# EDGAR_00.net
KiCad netlist of a schematic drawn in Altium Designer
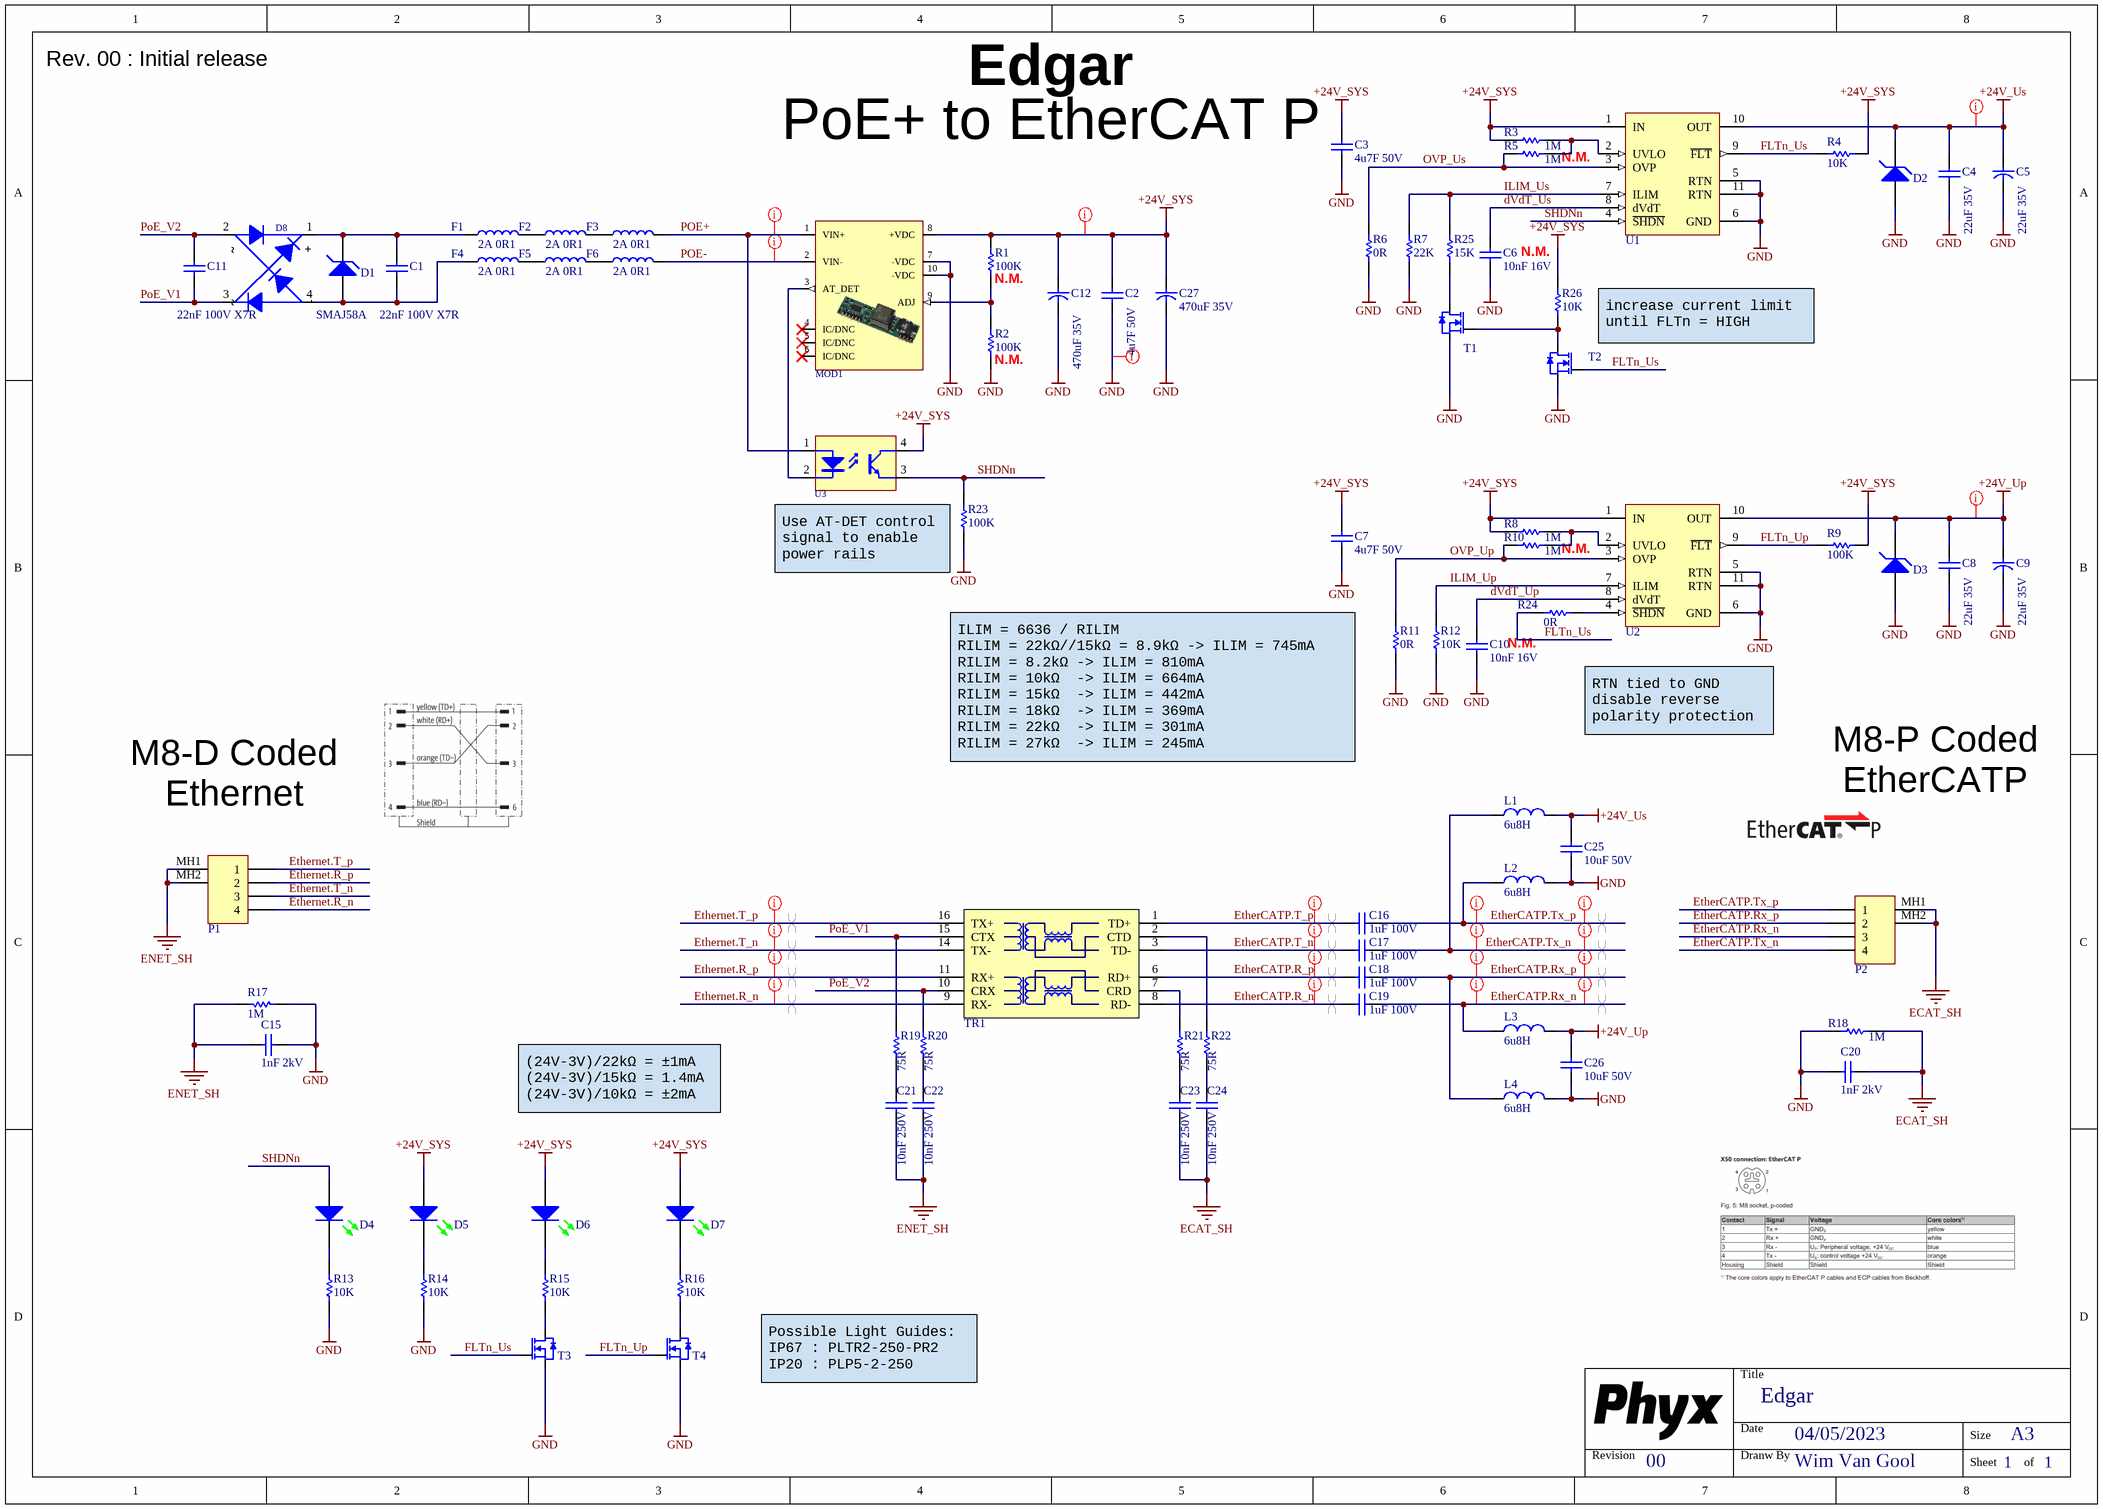
[diagram p0: EDGAR_00.SchDoc]

(export (version "E")
  (design (tool "Eeschema 10.0.6"))
  (components
    (comp (ref "C1")
      (value "22nF 100V X7R")
      (footprint "C0603_N")
      (description "Capacitor Ceramic")
      (fields (field (name "Comment") "CAP_CERAMIC"))
      (libsource (lib "Phyx_Components") (part "CAP_CERAMIC"))
    )
    (comp (ref "C2")
      (value "4u7F 50V")
      (footprint "C1210_N")
      (description "Capacitor Ceramic")
      (fields (field (name "Comment") "CAP_CERAMIC"))
      (libsource (lib "Phyx_Components") (part "CAP_CERAMIC"))
    )
    (comp (ref "C3")
      (value "4u7F 50V")
      (footprint "C1210_N")
      (description "Capacitor Ceramic")
      (fields (field (name "Comment") "CAP_CERAMIC"))
      (libsource (lib "Phyx_Components") (part "CAP_CERAMIC"))
    )
    (comp (ref "C4")
      (value "22uF 35V")
      (footprint "C1206_N")
      (description "Capacitor Ceramic")
      (fields (field (name "Comment") "CAP_CERAMIC"))
      (libsource (lib "Phyx_Components") (part "CAP_CERAMIC"))
    )
    (comp (ref "C5")
      (value "22uF 35V")
      (footprint "C6.6x5.4")
      (description "Capacitor electrolyt")
      (fields (field (name "Comment") "CAP_POL"))
      (libsource (lib "Phyx_Components") (part "CAP_POL"))
    )
    (comp (ref "C6")
      (value "10nF 16V")
      (footprint "C0603_N")
      (description "Capacitor Ceramic")
      (fields (field (name "Comment") "CAP_CERAMIC"))
      (libsource (lib "Phyx_Components") (part "CAP_CERAMIC"))
    )
    (comp (ref "C7")
      (value "4u7F 50V")
      (footprint "C1210_N")
      (description "Capacitor Ceramic")
      (fields (field (name "Comment") "CAP_CERAMIC"))
      (libsource (lib "Phyx_Components") (part "CAP_CERAMIC"))
    )
    (comp (ref "C8")
      (value "22uF 35V")
      (footprint "C1206_N")
      (description "Capacitor Ceramic")
      (fields (field (name "Comment") "CAP_CERAMIC"))
      (libsource (lib "Phyx_Components") (part "CAP_CERAMIC"))
    )
    (comp (ref "C9")
      (value "22uF 35V")
      (footprint "C6.6x5.4")
      (description "Capacitor electrolyt")
      (fields (field (name "Comment") "CAP_POL"))
      (libsource (lib "Phyx_Components") (part "CAP_POL"))
    )
    (comp (ref "C10")
      (value "10nF 16V")
      (footprint "C0603_N")
      (description "Capacitor Ceramic")
      (fields (field (name "Comment") "CAP_CERAMIC"))
      (libsource (lib "Phyx_Components") (part "CAP_CERAMIC"))
    )
    (comp (ref "C11")
      (value "22nF 100V X7R")
      (footprint "C0603_N")
      (description "Capacitor Ceramic")
      (fields (field (name "Comment") "CAP_CERAMIC"))
      (libsource (lib "Phyx_Components") (part "CAP_CERAMIC"))
    )
    (comp (ref "C12")
      (value "470uF 35V")
      (footprint "C10x10.2")
      (description "Capacitor electrolyt")
      (fields (field (name "Comment") "CAP_POL"))
      (libsource (lib "Phyx_Components") (part "CAP_POL"))
    )
    (comp (ref "C15")
      (value "1nF 2kV")
      (footprint "C1206_N")
      (description "Capacitor Ceramic")
      (fields (field (name "Comment") "CAP_CERAMIC"))
      (libsource (lib "Phyx_Components") (part "CAP_CERAMIC"))
    )
    (comp (ref "C16")
      (value "1uF 100V")
      (footprint "C1206_N")
      (description "Capacitor Ceramic")
      (fields (field (name "Comment") "CAP_CERAMIC"))
      (libsource (lib "Phyx_Components") (part "CAP_CERAMIC"))
    )
    (comp (ref "C17")
      (value "1uF 100V")
      (footprint "C1206_N")
      (description "Capacitor Ceramic")
      (fields (field (name "Comment") "CAP_CERAMIC"))
      (libsource (lib "Phyx_Components") (part "CAP_CERAMIC"))
    )
    (comp (ref "C18")
      (value "1uF 100V")
      (footprint "C1206_N")
      (description "Capacitor Ceramic")
      (fields (field (name "Comment") "CAP_CERAMIC"))
      (libsource (lib "Phyx_Components") (part "CAP_CERAMIC"))
    )
    (comp (ref "C19")
      (value "1uF 100V")
      (footprint "C1206_N")
      (description "Capacitor Ceramic")
      (fields (field (name "Comment") "CAP_CERAMIC"))
      (libsource (lib "Phyx_Components") (part "CAP_CERAMIC"))
    )
    (comp (ref "C20")
      (value "1nF 2kV")
      (footprint "C1206_N")
      (description "Capacitor Ceramic")
      (fields (field (name "Comment") "CAP_CERAMIC"))
      (libsource (lib "Phyx_Components") (part "CAP_CERAMIC"))
    )
    (comp (ref "C21")
      (value "10nF 250V")
      (footprint "C1206_N")
      (description "Capacitor Ceramic")
      (fields (field (name "Comment") "CAP_CERAMIC"))
      (libsource (lib "Phyx_Components") (part "CAP_CERAMIC"))
    )
    (comp (ref "C22")
      (value "10nF 250V")
      (footprint "C1206_N")
      (description "Capacitor Ceramic")
      (fields (field (name "Comment") "CAP_CERAMIC"))
      (libsource (lib "Phyx_Components") (part "CAP_CERAMIC"))
    )
    (comp (ref "C23")
      (value "10nF 250V")
      (footprint "C1206_N")
      (description "Capacitor Ceramic")
      (fields (field (name "Comment") "CAP_CERAMIC"))
      (libsource (lib "Phyx_Components") (part "CAP_CERAMIC"))
    )
    (comp (ref "C24")
      (value "10nF 250V")
      (footprint "C1206_N")
      (description "Capacitor Ceramic")
      (fields (field (name "Comment") "CAP_CERAMIC"))
      (libsource (lib "Phyx_Components") (part "CAP_CERAMIC"))
    )
    (comp (ref "C25")
      (value "10uF 50V")
      (footprint "C1206_N")
      (description "Capacitor Ceramic")
      (fields (field (name "Comment") "CAP_CERAMIC"))
      (libsource (lib "Phyx_Components") (part "CAP_CERAMIC"))
    )
    (comp (ref "C26")
      (value "10uF 50V")
      (footprint "C1206_N")
      (description "Capacitor Ceramic")
      (fields (field (name "Comment") "CAP_CERAMIC"))
      (libsource (lib "Phyx_Components") (part "CAP_CERAMIC"))
    )
    (comp (ref "C27")
      (value "470uF 35V")
      (footprint "C_12.5x14_5mm")
      (description "Capacitor electrolyt")
      (fields (field (name "Comment") "URZ1V471MHD"))
      (libsource (lib "Phyx_Components") (part "CAP_POL"))
    )
    (comp (ref "D1")
      (value "SMAJ58A")
      (footprint "SMA_AC")
      (fields (field (name "Comment") "TVS Diode 58V 400W Unidirectional DO-214AC SMA"))
      (libsource (lib "Phyx_Components") (part "TVS_AC"))
    )
    (comp (ref "D2")
      (value "TVS Diode 24V 400W Unidirectional DO-214AC SMA")
      (footprint "SMA_AC")
      (description "=Description")
      (libsource (lib "Phyx_Components") (part "TVS_AC"))
    )
    (comp (ref "D3")
      (value "TVS Diode 24V 400W Unidirectional DO-214AC SMA")
      (footprint "SMA_AC")
      (description "=Description")
      (libsource (lib "Phyx_Components") (part "TVS_AC"))
    )
    (comp (ref "D4")
      (value "Default 0805 Green LED")
      (footprint "LED_0805_GR")
      (description "=Description")
      (libsource (lib "Phyx_Components") (part "LED_GREEN"))
    )
    (comp (ref "D5")
      (value "Default 0805 Green LED")
      (footprint "LED_0805_GR")
      (description "=Description")
      (libsource (lib "Phyx_Components") (part "LED_GREEN"))
    )
    (comp (ref "D6")
      (value "Default 0805 Green LED")
      (footprint "LED_0805_GR")
      (description "=Description")
      (libsource (lib "Phyx_Components") (part "LED_GREEN"))
    )
    (comp (ref "D7")
      (value "Default 0805 Green LED")
      (footprint "LED_0805_GR")
      (description "=Description")
      (libsource (lib "Phyx_Components") (part "LED_GREEN"))
    )
    (comp (ref "D8")
      (value "Bridge Rectifier 100V 2A CD-HD201")
      (footprint "BRNS_CD_HD2x")
      (description "=Description")
      (libsource (lib "Phyx_Components") (part "BRNS_CD_HD2x"))
    )
    (comp (ref "F1")
      (value "2A 0R1")
      (footprint "L0805")
      (fields (field (name "Comment") "FERRITE"))
      (libsource (lib "Phyx_Components") (part "FERRITE"))
    )
    (comp (ref "F2")
      (value "2A 0R1")
      (footprint "L0805")
      (fields (field (name "Comment") "FERRITE"))
      (libsource (lib "Phyx_Components") (part "FERRITE"))
    )
    (comp (ref "F3")
      (value "2A 0R1")
      (footprint "L0805")
      (fields (field (name "Comment") "FERRITE"))
      (libsource (lib "Phyx_Components") (part "FERRITE"))
    )
    (comp (ref "F4")
      (value "2A 0R1")
      (footprint "L0805")
      (fields (field (name "Comment") "FERRITE"))
      (libsource (lib "Phyx_Components") (part "FERRITE"))
    )
    (comp (ref "F5")
      (value "2A 0R1")
      (footprint "L0805")
      (fields (field (name "Comment") "FERRITE"))
      (libsource (lib "Phyx_Components") (part "FERRITE"))
    )
    (comp (ref "F6")
      (value "2A 0R1")
      (footprint "L0805")
      (fields (field (name "Comment") "FERRITE"))
      (libsource (lib "Phyx_Components") (part "FERRITE"))
    )
    (comp (ref "L1")
      (value "6u8H")
      (footprint "WE_WE-LHMI_5020")
      (fields (field (name "Comment") "74437334068"))
      (libsource (lib "Phyx_Components") (part "INDUCTOR"))
    )
    (comp (ref "L2")
      (value "6u8H")
      (footprint "WE_WE-LHMI_5020")
      (fields (field (name "Comment") "74437334068"))
      (libsource (lib "Phyx_Components") (part "INDUCTOR"))
    )
    (comp (ref "L3")
      (value "6u8H")
      (footprint "WE_WE-LHMI_5020")
      (fields (field (name "Comment") "74437334068"))
      (libsource (lib "Phyx_Components") (part "INDUCTOR"))
    )
    (comp (ref "L4")
      (value "6u8H")
      (footprint "WE_WE-LHMI_5020")
      (fields (field (name "Comment") "74437334068"))
      (libsource (lib "Phyx_Components") (part "INDUCTOR"))
    )
    (comp (ref "MOD1")
      (value "PoE+ Module 24V 30W 802.3at Silvertel Ag5424")
      (footprint "SIL_Ag5400")
      (description "=Description")
      (libsource (lib "Phyx_Components") (part "SIL_Ag5400"))
    )
    (comp (ref "P1")
      (value "Receptacle, M8, female, straight, 4 poles, D-coded, back wall-mounting, print contact, shielded, Industrial Ethernet")
      (footprint "ESCHA_8089337")
      (libsource (lib "Phyx_Components") (part "Header 4_MH2"))
    )
    (comp (ref "P2")
      (value "Receptacle, M8, female, straight, 4 poles, P-coded, back wall-mounting, print contact, shielded, EtherCATP")
      (footprint "ESCHA_8089341")
      (libsource (lib "") (part "Header 4_MH2_1"))
    )
    (comp (ref "R1")
      (value "100K")
      (footprint "R0603_N")
      (fields (field (name "Comment") "RESISTOR"))
      (libsource (lib "Phyx_Components") (part "RESISTOR"))
    )
    (comp (ref "R2")
      (value "100K")
      (footprint "R0603_N")
      (fields (field (name "Comment") "RESISTOR"))
      (libsource (lib "Phyx_Components") (part "RESISTOR"))
    )
    (comp (ref "R3")
      (value "1M")
      (footprint "R0603_N")
      (fields (field (name "Comment") "RESISTOR"))
      (libsource (lib "Phyx_Components") (part "RESISTOR"))
    )
    (comp (ref "R4")
      (value "10K")
      (footprint "R0603_N")
      (fields (field (name "Comment") "RESISTOR"))
      (libsource (lib "Phyx_Components") (part "RESISTOR"))
    )
    (comp (ref "R5")
      (value "1M")
      (footprint "R0603_N")
      (fields (field (name "Comment") "RESISTOR"))
      (libsource (lib "Phyx_Components") (part "RESISTOR"))
    )
    (comp (ref "R6")
      (value "0R")
      (footprint "R0603_N")
      (fields (field (name "Comment") "RESISTOR"))
      (libsource (lib "Phyx_Components") (part "RESISTOR"))
    )
    (comp (ref "R7")
      (value "22K")
      (footprint "R0603_N")
      (fields (field (name "Comment") "RESISTOR"))
      (libsource (lib "Phyx_Components") (part "RESISTOR"))
    )
    (comp (ref "R8")
      (value "1M")
      (footprint "R0603_N")
      (fields (field (name "Comment") "RESISTOR"))
      (libsource (lib "Phyx_Components") (part "RESISTOR"))
    )
    (comp (ref "R9")
      (value "100K")
      (footprint "R0603_N")
      (fields (field (name "Comment") "RESISTOR"))
      (libsource (lib "Phyx_Components") (part "RESISTOR"))
    )
    (comp (ref "R10")
      (value "1M")
      (footprint "R0603_N")
      (fields (field (name "Comment") "RESISTOR"))
      (libsource (lib "Phyx_Components") (part "RESISTOR"))
    )
    (comp (ref "R11")
      (value "0R")
      (footprint "R0603_N")
      (fields (field (name "Comment") "RESISTOR"))
      (libsource (lib "Phyx_Components") (part "RESISTOR"))
    )
    (comp (ref "R12")
      (value "10K")
      (footprint "R0603_N")
      (fields (field (name "Comment") "RESISTOR"))
      (libsource (lib "Phyx_Components") (part "RESISTOR"))
    )
    (comp (ref "R13")
      (value "10K")
      (footprint "R0603_N")
      (fields (field (name "Comment") "RESISTOR"))
      (libsource (lib "Phyx_Components") (part "RESISTOR"))
    )
    (comp (ref "R14")
      (value "10K")
      (footprint "R0603_N")
      (fields (field (name "Comment") "RESISTOR"))
      (libsource (lib "Phyx_Components") (part "RESISTOR"))
    )
    (comp (ref "R15")
      (value "10K")
      (footprint "R0603_N")
      (fields (field (name "Comment") "RESISTOR"))
      (libsource (lib "Phyx_Components") (part "RESISTOR"))
    )
    (comp (ref "R16")
      (value "10K")
      (footprint "R0603_N")
      (fields (field (name "Comment") "RESISTOR"))
      (libsource (lib "Phyx_Components") (part "RESISTOR"))
    )
    (comp (ref "R17")
      (value "1M")
      (footprint "R0603_N")
      (fields (field (name "Comment") "RESISTOR"))
      (libsource (lib "Phyx_Components") (part "RESISTOR"))
    )
    (comp (ref "R18")
      (value "1M")
      (footprint "R0603_N")
      (fields (field (name "Comment") "RESISTOR"))
      (libsource (lib "Phyx_Components") (part "RESISTOR"))
    )
    (comp (ref "R19")
      (value "75R")
      (footprint "R0603_N")
      (fields (field (name "Comment") "RESISTOR"))
      (libsource (lib "Phyx_Components") (part "RESISTOR"))
    )
    (comp (ref "R20")
      (value "75R")
      (footprint "R0603_N")
      (fields (field (name "Comment") "RESISTOR"))
      (libsource (lib "Phyx_Components") (part "RESISTOR"))
    )
    (comp (ref "R21")
      (value "75R")
      (footprint "R0603_N")
      (fields (field (name "Comment") "RESISTOR"))
      (libsource (lib "Phyx_Components") (part "RESISTOR"))
    )
    (comp (ref "R22")
      (value "75R")
      (footprint "R0603_N")
      (fields (field (name "Comment") "RESISTOR"))
      (libsource (lib "Phyx_Components") (part "RESISTOR"))
    )
    (comp (ref "R23")
      (value "100K")
      (footprint "R0603_N")
      (fields (field (name "Comment") "RESISTOR"))
      (libsource (lib "Phyx_Components") (part "RESISTOR"))
    )
    (comp (ref "R24")
      (value "0R")
      (footprint "R0603_N")
      (fields (field (name "Comment") "RESISTOR"))
      (libsource (lib "Phyx_Components") (part "RESISTOR"))
    )
    (comp (ref "R25")
      (value "15K")
      (footprint "R0603_N")
      (fields (field (name "Comment") "RESISTOR"))
      (libsource (lib "Phyx_Components") (part "RESISTOR"))
    )
    (comp (ref "R26")
      (value "10K")
      (footprint "R0603_N")
      (fields (field (name "Comment") "RESISTOR"))
      (libsource (lib "Phyx_Components") (part "RESISTOR"))
    )
    (comp (ref "T1")
      (value "0.12A N-Ch MOSFET 60V Vgs 2.5")
      (footprint "SOT23-3")
      (libsource (lib "Phyx_Components") (part "N_MOSFET_GSD"))
    )
    (comp (ref "T2")
      (value "0.12A N-Ch MOSFET 60V Vgs 2.5")
      (footprint "SOT23-3")
      (libsource (lib "Phyx_Components") (part "N_MOSFET_GSD"))
    )
    (comp (ref "T3")
      (value "0.12A N-Ch MOSFET 60V Vgs 2.5")
      (footprint "SOT23-3")
      (libsource (lib "Phyx_Components") (part "N_MOSFET_GSD"))
    )
    (comp (ref "T4")
      (value "0.12A N-Ch MOSFET 60V Vgs 2.5")
      (footprint "SOT23-3")
      (libsource (lib "Phyx_Components") (part "N_MOSFET_GSD"))
    )
    (comp (ref "TR1")
      (value "10/100 Ethernet transformer with720mA PoE")
      (footprint "WE_749012310")
      (description "=Description")
      (libsource (lib "Phyx_Components") (part "WE_749012310"))
    )
    (comp (ref "U1")
      (value "4.5-V to 60-V, 478mΩ, 0.025-0.88A eFuse, auto retry, input and output reverse polarity protection")
      (footprint "TI_DRC10")
      (description "=Description")
      (libsource (lib "Phyx_Components") (part "TI_TPS2662x"))
    )
    (comp (ref "U2")
      (value "4.5-V to 60-V, 478mΩ, 0.025-0.88A eFuse, auto retry, input and output reverse polarity protection")
      (footprint "TI_DRC10")
      (description "=Description")
      (libsource (lib "Phyx_Components") (part "TI_TPS2662x"))
    )
    (comp (ref "U3")
      (value "CTR 50~600, 35V Vce, 60mA, 3.75kV")
      (footprint "WE_WL-OCPT_SOP-4")
      (description "=Description")
      (libsource (lib "Phyx_Components") (part "OPTO_4"))
    )
  )
  (nets
    (net (code "1") (name "+24V_SYS") (class "Default")
      (node (ref "C12") (pin "1") (pinfunction "1_1") (pintype "passive"))
      (node (ref "C2") (pin "1") (pinfunction "1_1") (pintype "passive"))
      (node (ref "C27") (pin "1") (pinfunction "1_1") (pintype "passive"))
      (node (ref "C3") (pin "1") (pinfunction "1_1") (pintype "passive"))
      (node (ref "C7") (pin "1") (pinfunction "1_1") (pintype "passive"))
      (node (ref "D5") (pin "1") (pinfunction "A_1") (pintype "passive"))
      (node (ref "D6") (pin "1") (pinfunction "A_1") (pintype "passive"))
      (node (ref "D7") (pin "1") (pinfunction "A_1") (pintype "passive"))
      (node (ref "MOD1") (pin "8") (pinfunction "+VDC_8") (pintype "power_in"))
      (node (ref "R1") (pin "1") (pinfunction "1_1") (pintype "passive"))
      (node (ref "R26") (pin "1") (pinfunction "1_1") (pintype "passive"))
      (node (ref "R3") (pin "2") (pinfunction "2_2") (pintype "passive"))
      (node (ref "R4") (pin "1") (pinfunction "1_1") (pintype "passive"))
      (node (ref "R8") (pin "2") (pinfunction "2_2") (pintype "passive"))
      (node (ref "R9") (pin "1") (pinfunction "1_1") (pintype "passive"))
      (node (ref "U1") (pin "1") (pinfunction "IN_1") (pintype "power_in"))
      (node (ref "U2") (pin "1") (pinfunction "IN_1") (pintype "power_in"))
      (node (ref "U3") (pin "4") (pinfunction "C_4") (pintype "passive"))
    )
    (net (code "2") (name "+24V_Up") (class "Default")
      (node (ref "C26") (pin "1") (pinfunction "1_1") (pintype "passive"))
      (node (ref "C8") (pin "1") (pinfunction "1_1") (pintype "passive"))
      (node (ref "C9") (pin "1") (pinfunction "1_1") (pintype "passive"))
      (node (ref "D3") (pin "C") (pinfunction "C_C") (pintype "passive"))
      (node (ref "L3") (pin "2") (pinfunction "2_2") (pintype "passive"))
      (node (ref "U2") (pin "10") (pinfunction "OUT_10") (pintype "power_in"))
    )
    (net (code "3") (name "+24V_Us") (class "Default")
      (node (ref "C25") (pin "1") (pinfunction "1_1") (pintype "passive"))
      (node (ref "C4") (pin "1") (pinfunction "1_1") (pintype "passive"))
      (node (ref "C5") (pin "1") (pinfunction "1_1") (pintype "passive"))
      (node (ref "D2") (pin "C") (pinfunction "C_C") (pintype "passive"))
      (node (ref "L1") (pin "2") (pinfunction "2_2") (pintype "passive"))
      (node (ref "U1") (pin "10") (pinfunction "OUT_10") (pintype "power_in"))
    )
    (net (code "4") (name "/EtherCATP.R_n") (class "Default")
      (node (ref "C19") (pin "2") (pinfunction "2_2") (pintype "passive"))
      (node (ref "TR1") (pin "8") (pinfunction "RD-_8") (pintype "passive"))
    )
    (net (code "5") (name "/EtherCATP.R_p") (class "Default")
      (node (ref "C18") (pin "2") (pinfunction "2_2") (pintype "passive"))
      (node (ref "TR1") (pin "6") (pinfunction "RD+_6") (pintype "passive"))
    )
    (net (code "6") (name "/EtherCATP.Rx_n") (class "Default")
      (node (ref "C19") (pin "1") (pinfunction "1_1") (pintype "passive"))
      (node (ref "L3") (pin "1") (pinfunction "1_1") (pintype "passive"))
      (node (ref "P2") (pin "3") (pinfunction "3_3") (pintype "passive"))
    )
    (net (code "7") (name "/EtherCATP.Rx_p") (class "Default")
      (node (ref "C18") (pin "1") (pinfunction "1_1") (pintype "passive"))
      (node (ref "L4") (pin "1") (pinfunction "1_1") (pintype "passive"))
      (node (ref "P2") (pin "2") (pinfunction "2_2") (pintype "passive"))
    )
    (net (code "8") (name "/EtherCATP.T_n") (class "Default")
      (node (ref "C17") (pin "2") (pinfunction "2_2") (pintype "passive"))
      (node (ref "TR1") (pin "3") (pinfunction "TD-_3") (pintype "passive"))
    )
    (net (code "9") (name "/EtherCATP.T_p") (class "Default")
      (node (ref "C16") (pin "2") (pinfunction "2_2") (pintype "passive"))
      (node (ref "TR1") (pin "1") (pinfunction "TD+_1") (pintype "passive"))
    )
    (net (code "10") (name "/EtherCATP.Tx_n") (class "Default")
      (node (ref "C17") (pin "1") (pinfunction "1_1") (pintype "passive"))
      (node (ref "L1") (pin "1") (pinfunction "1_1") (pintype "passive"))
      (node (ref "P2") (pin "4") (pinfunction "4_4") (pintype "passive"))
    )
    (net (code "11") (name "/EtherCATP.Tx_p") (class "Default")
      (node (ref "C16") (pin "1") (pinfunction "1_1") (pintype "passive"))
      (node (ref "L2") (pin "1") (pinfunction "1_1") (pintype "passive"))
      (node (ref "P2") (pin "1") (pinfunction "1_1") (pintype "passive"))
    )
    (net (code "12") (name "/Ethernet.R_n") (class "Default")
      (node (ref "P1") (pin "4") (pinfunction "4_4") (pintype "passive"))
      (node (ref "TR1") (pin "9") (pinfunction "RX-_9") (pintype "passive"))
    )
    (net (code "13") (name "/Ethernet.R_p") (class "Default")
      (node (ref "P1") (pin "2") (pinfunction "2_2") (pintype "passive"))
      (node (ref "TR1") (pin "11") (pinfunction "RX+_11") (pintype "passive"))
    )
    (net (code "14") (name "/Ethernet.T_n") (class "Default")
      (node (ref "P1") (pin "3") (pinfunction "3_3") (pintype "passive"))
      (node (ref "TR1") (pin "14") (pinfunction "TX-_14") (pintype "passive"))
    )
    (net (code "15") (name "/Ethernet.T_p") (class "Default")
      (node (ref "P1") (pin "1") (pinfunction "1_1") (pintype "passive"))
      (node (ref "TR1") (pin "16") (pinfunction "TX+_16") (pintype "passive"))
    )
    (net (code "16") (name "/FLTn_Up") (class "Default")
      (node (ref "R9") (pin "2") (pinfunction "2_2") (pintype "passive"))
      (node (ref "T4") (pin "1") (pinfunction "G_1") (pintype "passive"))
      (node (ref "U2") (pin "9") (pinfunction "~{FLT}_9") (pintype "output"))
    )
    (net (code "17") (name "/FLTn_Us") (class "Default")
      (node (ref "R24") (pin "1") (pinfunction "1_1") (pintype "passive"))
      (node (ref "R4") (pin "2") (pinfunction "2_2") (pintype "passive"))
      (node (ref "T2") (pin "1") (pinfunction "G_1") (pintype "passive"))
      (node (ref "T3") (pin "1") (pinfunction "G_1") (pintype "passive"))
      (node (ref "U1") (pin "9") (pinfunction "~{FLT}_9") (pintype "output"))
    )
    (net (code "18") (name "/ILIM_Up") (class "Default")
      (node (ref "R12") (pin "1") (pinfunction "1_1") (pintype "passive"))
      (node (ref "U2") (pin "7") (pinfunction "ILIM_7") (pintype "input"))
    )
    (net (code "19") (name "/ILIM_Us") (class "Default")
      (node (ref "R25") (pin "1") (pinfunction "1_1") (pintype "passive"))
      (node (ref "R7") (pin "1") (pinfunction "1_1") (pintype "passive"))
      (node (ref "U1") (pin "7") (pinfunction "ILIM_7") (pintype "input"))
    )
    (net (code "20") (name "/OVP_Up") (class "Default")
      (node (ref "R10") (pin "2") (pinfunction "2_2") (pintype "passive"))
      (node (ref "R11") (pin "1") (pinfunction "1_1") (pintype "passive"))
      (node (ref "U2") (pin "3") (pinfunction "OVP_3") (pintype "input"))
    )
    (net (code "21") (name "/OVP_Us") (class "Default")
      (node (ref "R5") (pin "2") (pinfunction "2_2") (pintype "passive"))
      (node (ref "R6") (pin "1") (pinfunction "1_1") (pintype "passive"))
      (node (ref "U1") (pin "3") (pinfunction "OVP_3") (pintype "input"))
    )
    (net (code "22") (name "/POE+") (class "Default")
      (node (ref "F3") (pin "2") (pinfunction "2_2") (pintype "passive"))
      (node (ref "MOD1") (pin "1") (pinfunction "VIN+_1") (pintype "power_in"))
      (node (ref "U3") (pin "1") (pinfunction "A_1") (pintype "passive"))
    )
    (net (code "23") (name "/POE-") (class "Default")
      (node (ref "F6") (pin "2") (pinfunction "2_2") (pintype "passive"))
      (node (ref "MOD1") (pin "2") (pinfunction "VIN-_2") (pintype "power_in"))
    )
    (net (code "24") (name "/PoE_V1") (class "Default")
      (node (ref "C11") (pin "2") (pinfunction "2_2") (pintype "passive"))
      (node (ref "D8") (pin "3") (pinfunction "C_3") (pintype "passive"))
      (node (ref "R19") (pin "1") (pinfunction "1_1") (pintype "passive"))
      (node (ref "TR1") (pin "15") (pinfunction "CTX_15") (pintype "passive"))
    )
    (net (code "25") (name "/PoE_V2") (class "Default")
      (node (ref "C11") (pin "1") (pinfunction "1_1") (pintype "passive"))
      (node (ref "D8") (pin "2") (pinfunction "A_2") (pintype "passive"))
      (node (ref "R20") (pin "1") (pinfunction "1_1") (pintype "passive"))
      (node (ref "TR1") (pin "10") (pinfunction "CRX_10") (pintype "passive"))
    )
    (net (code "26") (name "/SHDNn") (class "Default")
      (node (ref "D4") (pin "1") (pinfunction "A_1") (pintype "passive"))
      (node (ref "R23") (pin "1") (pinfunction "1_1") (pintype "passive"))
      (node (ref "U1") (pin "4") (pinfunction "~{SHDN}_4") (pintype "input"))
      (node (ref "U3") (pin "3") (pinfunction "E_3") (pintype "passive"))
    )
    (net (code "27") (name "/dVdT_Up") (class "Default")
      (node (ref "C10") (pin "1") (pinfunction "1_1") (pintype "passive"))
      (node (ref "U2") (pin "8") (pinfunction "dVdT_8") (pintype "input"))
    )
    (net (code "28") (name "/dVdT_Us") (class "Default")
      (node (ref "C6") (pin "1") (pinfunction "1_1") (pintype "passive"))
      (node (ref "U1") (pin "8") (pinfunction "dVdT_8") (pintype "input"))
    )
    (net (code "29") (name "ECAT_SH") (class "Default")
      (node (ref "C20") (pin "1") (pinfunction "1_1") (pintype "passive"))
      (node (ref "C23") (pin "2") (pinfunction "2_2") (pintype "passive"))
      (node (ref "C24") (pin "2") (pinfunction "2_2") (pintype "passive"))
      (node (ref "P2") (pin "MH1") (pinfunction "MH1_MH1") (pintype "passive"))
      (node (ref "P2") (pin "MH2") (pinfunction "MH2_MH2") (pintype "passive"))
      (node (ref "R18") (pin "1") (pinfunction "1_1") (pintype "passive"))
    )
    (net (code "30") (name "ENET_SH") (class "Default")
      (node (ref "C15") (pin "1") (pinfunction "1_1") (pintype "passive"))
      (node (ref "C21") (pin "2") (pinfunction "2_2") (pintype "passive"))
      (node (ref "C22") (pin "2") (pinfunction "2_2") (pintype "passive"))
      (node (ref "P1") (pin "MH1") (pinfunction "MH1_MH1") (pintype "passive"))
      (node (ref "P1") (pin "MH2") (pinfunction "MH2_MH2") (pintype "passive"))
      (node (ref "R17") (pin "1") (pinfunction "1_1") (pintype "passive"))
    )
    (net (code "31") (name "GND") (class "Default")
      (node (ref "C10") (pin "2") (pinfunction "2_2") (pintype "passive"))
      (node (ref "C12") (pin "2") (pinfunction "2_2") (pintype "passive"))
      (node (ref "C15") (pin "2") (pinfunction "2_2") (pintype "passive"))
      (node (ref "C2") (pin "2") (pinfunction "2_2") (pintype "passive"))
      (node (ref "C20") (pin "2") (pinfunction "2_2") (pintype "passive"))
      (node (ref "C25") (pin "2") (pinfunction "2_2") (pintype "passive"))
      (node (ref "C26") (pin "2") (pinfunction "2_2") (pintype "passive"))
      (node (ref "C27") (pin "2") (pinfunction "2_2") (pintype "passive"))
      (node (ref "C3") (pin "2") (pinfunction "2_2") (pintype "passive"))
      (node (ref "C4") (pin "2") (pinfunction "2_2") (pintype "passive"))
      (node (ref "C5") (pin "2") (pinfunction "2_2") (pintype "passive"))
      (node (ref "C6") (pin "2") (pinfunction "2_2") (pintype "passive"))
      (node (ref "C7") (pin "2") (pinfunction "2_2") (pintype "passive"))
      (node (ref "C8") (pin "2") (pinfunction "2_2") (pintype "passive"))
      (node (ref "C9") (pin "2") (pinfunction "2_2") (pintype "passive"))
      (node (ref "D2") (pin "A") (pinfunction "A_A") (pintype "passive"))
      (node (ref "D3") (pin "A") (pinfunction "A_A") (pintype "passive"))
      (node (ref "L2") (pin "2") (pinfunction "2_2") (pintype "passive"))
      (node (ref "L4") (pin "2") (pinfunction "2_2") (pintype "passive"))
      (node (ref "MOD1") (pin "10") (pinfunction "-VDC_10") (pintype "power_in"))
      (node (ref "MOD1") (pin "7") (pinfunction "-VDC_7") (pintype "power_in"))
      (node (ref "R11") (pin "2") (pinfunction "2_2") (pintype "passive"))
      (node (ref "R12") (pin "2") (pinfunction "2_2") (pintype "passive"))
      (node (ref "R13") (pin "2") (pinfunction "2_2") (pintype "passive"))
      (node (ref "R14") (pin "2") (pinfunction "2_2") (pintype "passive"))
      (node (ref "R17") (pin "2") (pinfunction "2_2") (pintype "passive"))
      (node (ref "R18") (pin "2") (pinfunction "2_2") (pintype "passive"))
      (node (ref "R2") (pin "2") (pinfunction "2_2") (pintype "passive"))
      (node (ref "R23") (pin "2") (pinfunction "2_2") (pintype "passive"))
      (node (ref "R6") (pin "2") (pinfunction "2_2") (pintype "passive"))
      (node (ref "R7") (pin "2") (pinfunction "2_2") (pintype "passive"))
      (node (ref "T1") (pin "2") (pinfunction "S_2") (pintype "passive"))
      (node (ref "T2") (pin "2") (pinfunction "S_2") (pintype "passive"))
      (node (ref "T3") (pin "2") (pinfunction "S_2") (pintype "passive"))
      (node (ref "T4") (pin "2") (pinfunction "S_2") (pintype "passive"))
      (node (ref "U1") (pin "11") (pinfunction "RTN_11") (pintype "power_in"))
      (node (ref "U1") (pin "5") (pinfunction "RTN_5") (pintype "power_in"))
      (node (ref "U1") (pin "6") (pinfunction "GND_6") (pintype "power_in"))
      (node (ref "U2") (pin "11") (pinfunction "RTN_11") (pintype "power_in"))
      (node (ref "U2") (pin "5") (pinfunction "RTN_5") (pintype "power_in"))
      (node (ref "U2") (pin "6") (pinfunction "GND_6") (pintype "power_in"))
    )
    (net (code "32") (name "Net-(C1-Pad1)") (class "Default")
      (node (ref "C1") (pin "1") (pinfunction "1_1") (pintype "passive"))
      (node (ref "D1") (pin "C") (pinfunction "C_C") (pintype "passive"))
      (node (ref "D8") (pin "1") (pinfunction "C_1") (pintype "passive"))
      (node (ref "F1") (pin "1") (pinfunction "1_1") (pintype "passive"))
    )
    (net (code "33") (name "Net-(C1-Pad2)") (class "Default")
      (node (ref "C1") (pin "2") (pinfunction "2_2") (pintype "passive"))
      (node (ref "D1") (pin "A") (pinfunction "A_A") (pintype "passive"))
      (node (ref "D8") (pin "4") (pinfunction "A_4") (pintype "passive"))
      (node (ref "F4") (pin "1") (pinfunction "1_1") (pintype "passive"))
    )
    (net (code "34") (name "Net-(C21-Pad1)") (class "Default")
      (node (ref "C21") (pin "1") (pinfunction "1_1") (pintype "passive"))
      (node (ref "R19") (pin "2") (pinfunction "2_2") (pintype "passive"))
    )
    (net (code "35") (name "Net-(C22-Pad1)") (class "Default")
      (node (ref "C22") (pin "1") (pinfunction "1_1") (pintype "passive"))
      (node (ref "R20") (pin "2") (pinfunction "2_2") (pintype "passive"))
    )
    (net (code "36") (name "Net-(C23-Pad1)") (class "Default")
      (node (ref "C23") (pin "1") (pinfunction "1_1") (pintype "passive"))
      (node (ref "R21") (pin "2") (pinfunction "2_2") (pintype "passive"))
    )
    (net (code "37") (name "Net-(C24-Pad1)") (class "Default")
      (node (ref "C24") (pin "1") (pinfunction "1_1") (pintype "passive"))
      (node (ref "R22") (pin "2") (pinfunction "2_2") (pintype "passive"))
    )
    (net (code "38") (name "Net-(D4-K)") (class "Default")
      (node (ref "D4") (pin "2") (pinfunction "K_2") (pintype "passive"))
      (node (ref "R13") (pin "1") (pinfunction "1_1") (pintype "passive"))
    )
    (net (code "39") (name "Net-(D5-K)") (class "Default")
      (node (ref "D5") (pin "2") (pinfunction "K_2") (pintype "passive"))
      (node (ref "R14") (pin "1") (pinfunction "1_1") (pintype "passive"))
    )
    (net (code "40") (name "Net-(D6-K)") (class "Default")
      (node (ref "D6") (pin "2") (pinfunction "K_2") (pintype "passive"))
      (node (ref "R15") (pin "1") (pinfunction "1_1") (pintype "passive"))
    )
    (net (code "41") (name "Net-(D7-K)") (class "Default")
      (node (ref "D7") (pin "2") (pinfunction "K_2") (pintype "passive"))
      (node (ref "R16") (pin "1") (pinfunction "1_1") (pintype "passive"))
    )
    (net (code "42") (name "Net-(F1-Pad2)") (class "Default")
      (node (ref "F1") (pin "2") (pinfunction "2_2") (pintype "passive"))
      (node (ref "F2") (pin "1") (pinfunction "1_1") (pintype "passive"))
    )
    (net (code "43") (name "Net-(F2-Pad2)") (class "Default")
      (node (ref "F2") (pin "2") (pinfunction "2_2") (pintype "passive"))
      (node (ref "F3") (pin "1") (pinfunction "1_1") (pintype "passive"))
    )
    (net (code "44") (name "Net-(F4-Pad2)") (class "Default")
      (node (ref "F4") (pin "2") (pinfunction "2_2") (pintype "passive"))
      (node (ref "F5") (pin "1") (pinfunction "1_1") (pintype "passive"))
    )
    (net (code "45") (name "Net-(F5-Pad2)") (class "Default")
      (node (ref "F5") (pin "2") (pinfunction "2_2") (pintype "passive"))
      (node (ref "F6") (pin "1") (pinfunction "1_1") (pintype "passive"))
    )
    (net (code "46") (name "Net-(MOD1-ADJ)") (class "Default")
      (node (ref "MOD1") (pin "9") (pinfunction "ADJ_9") (pintype "input"))
      (node (ref "R1") (pin "2") (pinfunction "2_2") (pintype "passive"))
      (node (ref "R2") (pin "1") (pinfunction "1_1") (pintype "passive"))
    )
    (net (code "47") (name "Net-(MOD1-AT_DET)") (class "Default")
      (node (ref "MOD1") (pin "3") (pinfunction "AT_DET_3") (pintype "output"))
      (node (ref "U3") (pin "2") (pinfunction "K_2") (pintype "passive"))
    )
    (net (code "48") (name "Net-(T1-D)") (class "Default")
      (node (ref "R25") (pin "2") (pinfunction "2_2") (pintype "passive"))
      (node (ref "T1") (pin "3") (pinfunction "D_3") (pintype "passive"))
    )
    (net (code "49") (name "Net-(T1-G)") (class "Default")
      (node (ref "R26") (pin "2") (pinfunction "2_2") (pintype "passive"))
      (node (ref "T1") (pin "1") (pinfunction "G_1") (pintype "passive"))
      (node (ref "T2") (pin "3") (pinfunction "D_3") (pintype "passive"))
    )
    (net (code "50") (name "Net-(T3-D)") (class "Default")
      (node (ref "R15") (pin "2") (pinfunction "2_2") (pintype "passive"))
      (node (ref "T3") (pin "3") (pinfunction "D_3") (pintype "passive"))
    )
    (net (code "51") (name "Net-(T4-D)") (class "Default")
      (node (ref "R16") (pin "2") (pinfunction "2_2") (pintype "passive"))
      (node (ref "T4") (pin "3") (pinfunction "D_3") (pintype "passive"))
    )
    (net (code "52") (name "Net-(TR1-CRD)") (class "Default")
      (node (ref "R21") (pin "1") (pinfunction "1_1") (pintype "passive"))
      (node (ref "TR1") (pin "7") (pinfunction "CRD_7") (pintype "passive"))
    )
    (net (code "53") (name "Net-(TR1-CTD)") (class "Default")
      (node (ref "R22") (pin "1") (pinfunction "1_1") (pintype "passive"))
      (node (ref "TR1") (pin "2") (pinfunction "CTD_2") (pintype "passive"))
    )
    (net (code "54") (name "Net-(U1-UVLO)") (class "Default")
      (node (ref "R3") (pin "1") (pinfunction "1_1") (pintype "passive"))
      (node (ref "R5") (pin "1") (pinfunction "1_1") (pintype "passive"))
      (node (ref "U1") (pin "2") (pinfunction "UVLO_2") (pintype "input"))
    )
    (net (code "55") (name "Net-(U2-UVLO)") (class "Default")
      (node (ref "R10") (pin "1") (pinfunction "1_1") (pintype "passive"))
      (node (ref "R8") (pin "1") (pinfunction "1_1") (pintype "passive"))
      (node (ref "U2") (pin "2") (pinfunction "UVLO_2") (pintype "input"))
    )
    (net (code "56") (name "Net-(U2-~{SHDN})") (class "Default")
      (node (ref "R24") (pin "2") (pinfunction "2_2") (pintype "passive"))
      (node (ref "U2") (pin "4") (pinfunction "~{SHDN}_4") (pintype "input"))
    )
    (net (code "57") (name "unconnected-(MOD1-IC{slash}DNC-Pad4)") (class "Default")
      (node (ref "MOD1") (pin "4") (pinfunction "IC/DNC_4") (pintype "passive+no_connect"))
    )
    (net (code "58") (name "unconnected-(MOD1-IC{slash}DNC-Pad5)") (class "Default")
      (node (ref "MOD1") (pin "5") (pinfunction "IC/DNC_5") (pintype "passive+no_connect"))
    )
    (net (code "59") (name "unconnected-(MOD1-IC{slash}DNC-Pad6)") (class "Default")
      (node (ref "MOD1") (pin "6") (pinfunction "IC/DNC_6") (pintype "passive+no_connect"))
    )
  )
)
